# callisto_schematics_digital.net
KiCad netlist of a schematic drawn in Altium Designer
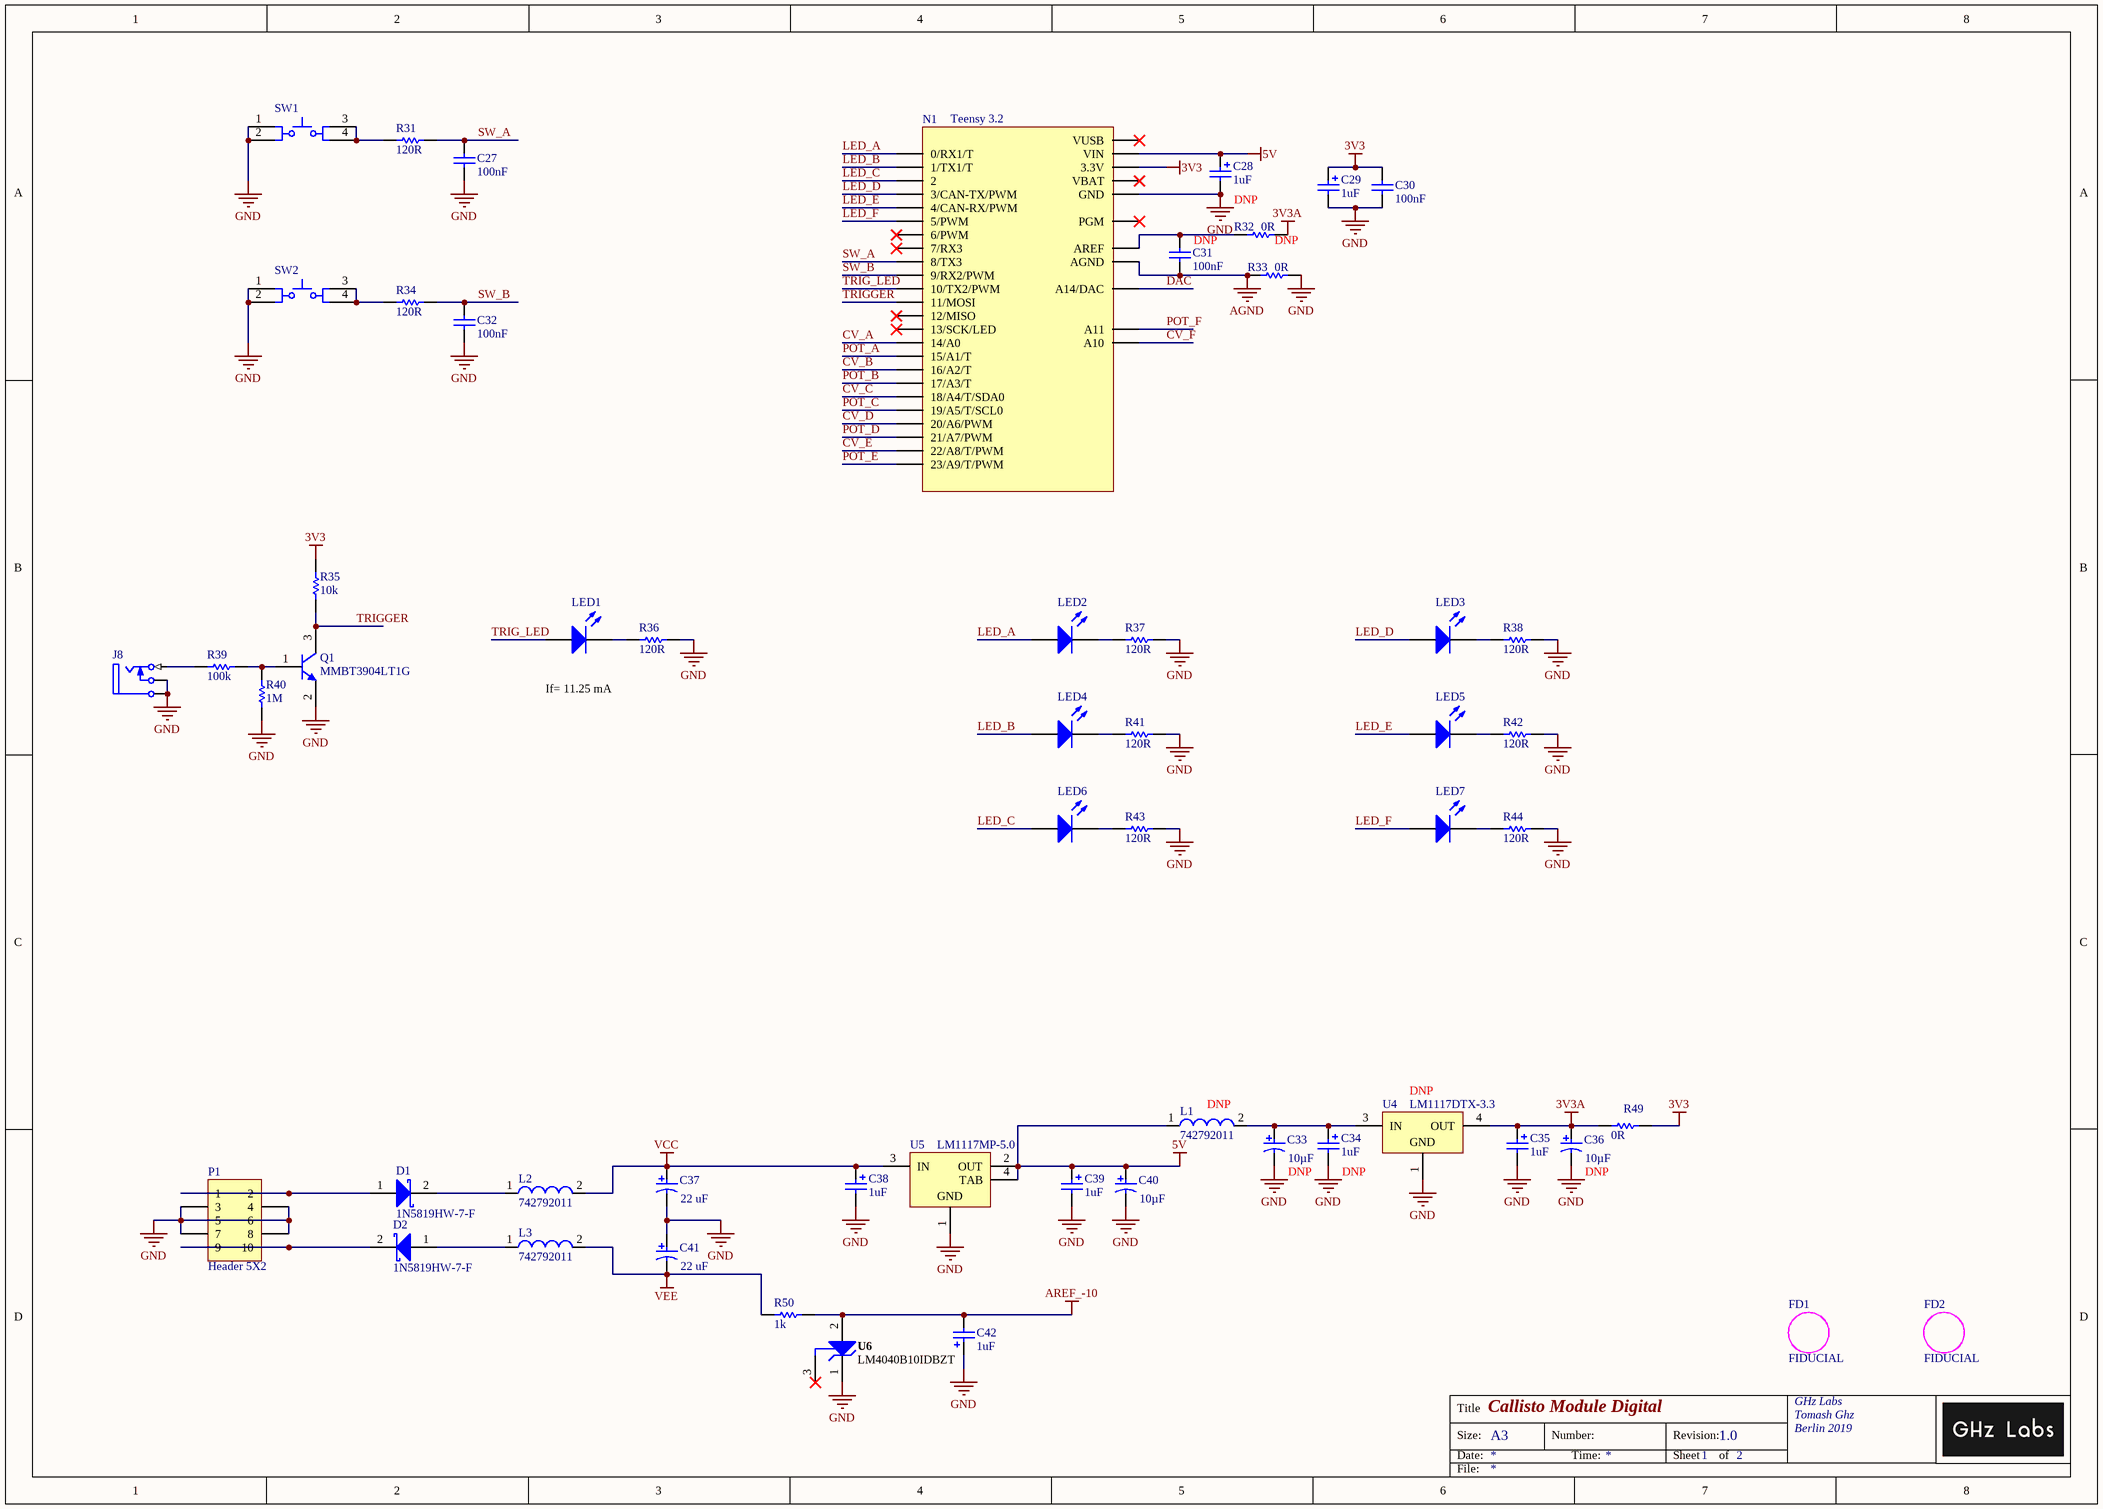
[diagram p0: callisto_schematics_digital.SchDoc]

(export (version "E")
  (design (tool "Eeschema 10.0.6"))
  (components
    (comp (ref "C27")
      (value "100nF")
      (footprint "GHzLabs_Parts:CAPA_0805")
      (description "Capacitor")
      (fields
        (field (name "PARTNUMBER") "C0805C104K4RAC")
        (field (name "MANUFACTURER") "KEMET")
        (field (name "PUBLISHER") "Altium Limited")
      )
      (libsource (lib "Miscellaneous Devices") (part "Cap"))
    )
    (comp (ref "C28")
      (value "1uF")
      (footprint "GHzLabs_Parts:CAPA_0805 Pol")
      (description "Polarized Capacitor")
      (fields
        (field (name "PARTNUMBER") "GRM21BR61C105KA01L")
        (field (name "MANUFACTURER") "Murata Electronics")
      )
      (libsource (lib "Miscellaneous Devices") (part "Cap Pol2"))
    )
    (comp (ref "C29")
      (value "1uF")
      (footprint "GHzLabs_Parts:CAPA_0805 Pol")
      (description "Polarized Capacitor")
      (fields
        (field (name "PARTNUMBER") "GRM21BR61C105KA01L")
        (field (name "MANUFACTURER") "Murata Electronics")
      )
      (libsource (lib "Miscellaneous Devices") (part "Cap Pol2"))
    )
    (comp (ref "C30")
      (value "100nF")
      (footprint "GHzLabs_Parts:CAPA_0805")
      (description "Capacitor")
      (fields
        (field (name "PARTNUMBER") "C0805C104K4RAC")
        (field (name "MANUFACTURER") "KEMET")
        (field (name "PUBLISHER") "Altium Limited")
      )
      (libsource (lib "Miscellaneous Devices") (part "Cap"))
    )
    (comp (ref "C31")
      (value "100nF")
      (footprint "GHzLabs_Parts:CAPA_0805")
      (description "Capacitor")
      (fields
        (field (name "PARTNUMBER") "C0805C104K4RAC")
        (field (name "MANUFACTURER") "KEMET")
        (field (name "PUBLISHER") "Altium Limited")
      )
      (libsource (lib "Miscellaneous Devices") (part "Cap"))
    )
    (comp (ref "C32")
      (value "100nF")
      (footprint "GHzLabs_Parts:CAPA_0805")
      (description "Capacitor")
      (fields
        (field (name "PARTNUMBER") "C0805C104K4RAC")
        (field (name "MANUFACTURER") "KEMET")
        (field (name "PUBLISHER") "Altium Limited")
      )
      (libsource (lib "Miscellaneous Devices") (part "Cap"))
    )
    (comp (ref "C33")
      (value "EEE-FK1V100UR")
      (footprint "PNSC-FK-V-B_V")
      (fields (field (name "MANUFACTURER") "Panasonic") (field (name "CAPACITANCE") "10µF"))
      (libsource (lib "Altium Content Vault") (part "CMP-2000-06211-1"))
    )
    (comp (ref "C34")
      (value "1uF")
      (footprint "GHzLabs_Parts:CAPA_0805 Pol")
      (description "Polarized Capacitor")
      (fields
        (field (name "PARTNUMBER") "GRM21BR61C105KA01L")
        (field (name "MANUFACTURER") "Murata Electronics")
      )
      (libsource (lib "Miscellaneous Devices") (part "Cap Pol2"))
    )
    (comp (ref "C35")
      (value "1uF")
      (footprint "GHzLabs_Parts:CAPA_0805 Pol")
      (description "Polarized Capacitor")
      (fields
        (field (name "PARTNUMBER") "GRM21BR61C105KA01L")
        (field (name "MANUFACTURER") "Murata Electronics")
      )
      (libsource (lib "Miscellaneous Devices") (part "Cap Pol2"))
    )
    (comp (ref "C36")
      (value "EEE-FK1V100UR")
      (footprint "PNSC-FK-V-B_V")
      (fields (field (name "MANUFACTURER") "Panasonic") (field (name "CAPACITANCE") "10µF"))
      (libsource (lib "Altium Content Vault") (part "CMP-2000-06211-1"))
    )
    (comp (ref "C37")
      (value "22uF Electrolytic Capacitor")
      (footprint "NIC-CAPA2-5X5.8_V")
      (fields
        (field (name "PARTNUMBER") "EEE-FK1V220R")
        (field (name "RATED CAPACITANCE") "22 uF")
        (field (name "MANUFACTURER") "Panasonic")
      )
      (libsource (lib "Altium Content Vault") (part "CMP-0687-00027-1"))
    )
    (comp (ref "C38")
      (value "1uF")
      (footprint "GHzLabs_Parts:CAPA_0805 Pol")
      (description "Polarized Capacitor")
      (fields
        (field (name "PARTNUMBER") "GRM21BR61C105KA01L")
        (field (name "MANUFACTURER") "Murata Electronics")
      )
      (libsource (lib "Miscellaneous Devices") (part "Cap Pol2"))
    )
    (comp (ref "C39")
      (value "1uF")
      (footprint "GHzLabs_Parts:CAPA_0805 Pol")
      (description "Polarized Capacitor")
      (fields
        (field (name "PARTNUMBER") "GRM21BR61C105KA01L")
        (field (name "MANUFACTURER") "Murata Electronics")
      )
      (libsource (lib "Miscellaneous Devices") (part "Cap Pol2"))
    )
    (comp (ref "C40")
      (value "10uF Electrolytic Capacitor")
      (footprint "PNSC-FK-V-B_V")
      (fields
        (field (name "MANUFACTURER") "Panasonic")
        (field (name "CAPACITANCE") "10µF")
        (field (name "PARTNUMBER") "EEE-FK1E100R")
      )
      (libsource (lib "Altium Content Vault") (part "CMP-2000-06211-1"))
    )
    (comp (ref "C41")
      (value "22uF Electrolytic Capacitor")
      (footprint "NIC-CAPA2-5X5.8_V")
      (fields
        (field (name "PARTNUMBER") "EEE-FK1V220R")
        (field (name "RATED CAPACITANCE") "22 uF")
        (field (name "MANUFACTURER") "Panasonic")
      )
      (libsource (lib "Altium Content Vault") (part "CMP-0687-00027-1"))
    )
    (comp (ref "C42")
      (value "1uF")
      (footprint "GHzLabs_Parts:CAPA_0805 Pol")
      (description "Polarized Capacitor")
      (fields
        (field (name "PARTNUMBER") "GRM21BR61C105KA01L")
        (field (name "MANUFACTURER") "Murata Electronics")
      )
      (libsource (lib "Miscellaneous Devices") (part "Cap Pol2"))
    )
    (comp (ref "D1")
      (value "1N5819HW-7-F")
      (footprint "DIOD-SOD-123-2_V")
      (fields (field (name "MANUFACTURER") "Diodes Inc"))
      (libsource (lib "Altium Content Vault") (part "DIOD-DSKY-A1K2-2"))
    )
    (comp (ref "D2")
      (value "1N5819HW-7-F")
      (footprint "DIOD-SOD-123-2_V")
      (fields (field (name "MANUFACTURER") "Diodes Inc"))
      (libsource (lib "Altium Content Vault") (part "DIOD-DSKY-A1K2-2"))
    )
    (comp (ref "FD1")
      (value "FIDUCIAL")
      (footprint "GHzLabs_Parts:FIDUCIAL")
      (description "Fiducial - Round 1.5 mm Top-Bottom")
      (fields (field (name "MANUFACTURER") "No Vendor"))
      (libsource (lib "GHzLabs_Parts") (part "FIDUCIAL_ROUND"))
    )
    (comp (ref "FD2")
      (value "FIDUCIAL")
      (footprint "GHzLabs_Parts:FIDUCIAL")
      (description "Fiducial - Round 1.5 mm Top-Bottom")
      (fields (field (name "MANUFACTURER") "No Vendor"))
      (libsource (lib "GHzLabs_Parts") (part "FIDUCIAL_ROUND"))
    )
    (comp (ref "J8")
      (value "Phonejack2 TN")
      (footprint "GHzLabs_Parts:Thonkiconn")
      (description "Jack Socket")
      (fields (field (name "PART") "ACJM-MV35-2S") (field (name "MANUFACTURER") "Thonk"))
      (libsource (lib "GHzLabs_Parts") (part "Phonejack2 TN"))
    )
    (comp (ref "L1")
      (value "742792011")
      (footprint "SMD-0805")
      (description "SMD EMI Suppression Ferrite Bead WE-CBF, Z = 10 Ohm")
      (libsource (lib "Altium Content Vault") (part "PAS-IND-INDUCTOR-2"))
    )
    (comp (ref "L2")
      (value "742792011")
      (footprint "SMD-0805")
      (description "SMD EMI Suppression Ferrite Bead WE-CBF, Z = 10 Ohm")
      (fields (field (name "MANUFACTURER") "Wurth Elektronik"))
      (libsource (lib "Altium Content Vault") (part "CMP-0220-00043-1"))
    )
    (comp (ref "L3")
      (value "742792011")
      (footprint "SMD-0805")
      (description "SMD EMI Suppression Ferrite Bead WE-CBF, Z = 10 Ohm")
      (fields (field (name "MANUFACTURER") "Wurth Elektronik"))
      (libsource (lib "Altium Content Vault") (part "CMP-0220-00043-1"))
    )
    (comp (ref "LED1")
      (value "WP424YDT")
      (footprint "Type 3mm")
      (description "THT LED round mono-color color lens, WL-TMRC, Bright Green")
      (fields (field (name "MANUFACTURER") "Kingbright"))
      (libsource (lib "Altium Content Vault") (part "CMP-1488-00001-1"))
    )
    (comp (ref "LED2")
      (value "WP424YDT")
      (footprint "Type 3mm")
      (description "THT LED round mono-color color lens, WL-TMRC, Bright Green")
      (fields (field (name "MANUFACTURER") "Kingbright"))
      (libsource (lib "Altium Content Vault") (part "CMP-1488-00001-1"))
    )
    (comp (ref "LED3")
      (value "WP424YDT")
      (footprint "Type 3mm")
      (description "THT LED round mono-color color lens, WL-TMRC, Bright Green")
      (fields (field (name "MANUFACTURER") "Kingbright"))
      (libsource (lib "Altium Content Vault") (part "CMP-1488-00001-1"))
    )
    (comp (ref "LED4")
      (value "WP424YDT")
      (footprint "Type 3mm")
      (description "THT LED round mono-color color lens, WL-TMRC, Bright Green")
      (fields (field (name "MANUFACTURER") "Kingbright"))
      (libsource (lib "Altium Content Vault") (part "CMP-1488-00001-1"))
    )
    (comp (ref "LED5")
      (value "WP424YDT")
      (footprint "Type 3mm")
      (description "THT LED round mono-color color lens, WL-TMRC, Bright Green")
      (fields (field (name "MANUFACTURER") "Kingbright"))
      (libsource (lib "Altium Content Vault") (part "CMP-1488-00001-1"))
    )
    (comp (ref "LED6")
      (value "WP424YDT")
      (footprint "Type 3mm")
      (description "THT LED round mono-color color lens, WL-TMRC, Bright Green")
      (fields (field (name "MANUFACTURER") "Kingbright"))
      (libsource (lib "Altium Content Vault") (part "CMP-1488-00001-1"))
    )
    (comp (ref "LED7")
      (value "WP424YDT")
      (footprint "Type 3mm")
      (description "THT LED round mono-color color lens, WL-TMRC, Bright Green")
      (fields (field (name "MANUFACTURER") "Kingbright"))
      (libsource (lib "Altium Content Vault") (part "CMP-1488-00001-1"))
    )
    (comp (ref "N1")
      (value "Teensy 3.2")
      (footprint "TEENSY_3.0-3.2&LC_ALL_PINS")
      (description "Teensy 3.2 MCU")
      (fields (field (name "PARTNUMBER") "DEV-13736") (field (name "MANUFACTURER") "SparkFun"))
      (libsource (lib "Teensy_3_and_LC_Series_Boards_v1") (part "TEENSY_3.1-3.2_ALL_PINS"))
    )
    (comp (ref "P1")
      (value "Header 5X2")
      (footprint "HDR2X5")
      (description "Header, 5-Pin, Dual row")
      (fields
        (field (name "PARTNUMBER") "67996-410HLF")
        (field (name "MANUFACTURER") "FCI Amphenol")
        (field (name "PUBLISHER") "Altium Limited")
      )
      (libsource (lib "Miscellaneous Connectors") (part "Header 5X2"))
    )
    (comp (ref "Q1")
      (value "MMBT3904LT1G")
      (footprint "ONSC-SOT-23-3-318-08_V")
      (description "General Purpose Transistor, NPN Silicon, 3-Pin SOT-23, Pb-Free, Tape and Reel")
      (fields (field (name "MANUFACTURER") "On Semiconductor"))
      (libsource (lib "Altium Content Vault") (part "ONSC-NPN-B1E2C3-3"))
    )
    (comp (ref "R31")
      (value "120R")
      (footprint "GHzLabs_Parts:RES_0805")
      (description "120R 0805")
      (fields (field (name "PARTNUMBER") "CRCW0805120RJNEA") (field (name "MANUFACTURER") "Vishay"))
      (libsource (lib "GHzLabs_Parts") (part "Resistor"))
    )
    (comp (ref "R32")
      (value "0R")
      (footprint "GHzLabs_Parts:RES_0805")
      (description "0R 0805")
      (fields (field (name "PARTNUMBER") "CRCW08050000Z0EA") (field (name "MANUFACTURER") "Vishay"))
      (libsource (lib "myParts") (part "Resistor"))
    )
    (comp (ref "R33")
      (value "0R")
      (footprint "GHzLabs_Parts:RES_0805")
      (description "0R 0805")
      (fields (field (name "PARTNUMBER") "CRCW08050000Z0EA") (field (name "MANUFACTURER") "Vishay"))
      (libsource (lib "myParts") (part "Resistor"))
    )
    (comp (ref "R34")
      (value "120R")
      (footprint "GHzLabs_Parts:RES_0805")
      (description "120R 0805")
      (fields (field (name "PARTNUMBER") "CRCW0805120RJNEA") (field (name "MANUFACTURER") "Vishay"))
      (libsource (lib "GHzLabs_Parts") (part "Resistor"))
    )
    (comp (ref "R35")
      (value "10k")
      (footprint "GHzLabs_Parts:RES_0805")
      (description "10k 0805")
      (fields (field (name "PARTNUMBER") "RR1220P-103-D") (field (name "MANUFACTURER") "Susumu"))
      (libsource (lib "GHzLabs_Parts") (part "Resistor"))
    )
    (comp (ref "R36")
      (value "120R")
      (footprint "GHzLabs_Parts:RES_0805")
      (description "120R 0805")
      (fields (field (name "PARTNUMBER") "CRCW0805120RJNEA") (field (name "MANUFACTURER") "Vishay"))
      (libsource (lib "GHzLabs_Parts") (part "Resistor"))
    )
    (comp (ref "R37")
      (value "120R")
      (footprint "GHzLabs_Parts:RES_0805")
      (description "120R 0805")
      (fields (field (name "PARTNUMBER") "CRCW0805120RJNEA") (field (name "MANUFACTURER") "Vishay"))
      (libsource (lib "GHzLabs_Parts") (part "Resistor"))
    )
    (comp (ref "R38")
      (value "120R")
      (footprint "GHzLabs_Parts:RES_0805")
      (description "120R 0805")
      (fields (field (name "PARTNUMBER") "CRCW0805120RJNEA") (field (name "MANUFACTURER") "Vishay"))
      (libsource (lib "GHzLabs_Parts") (part "Resistor"))
    )
    (comp (ref "R39")
      (value "100k")
      (footprint "GHzLabs_Parts:RES_0805")
      (description "100k 0805")
      (fields (field (name "PARTNUMBER") "RR1220P-104-D") (field (name "MANUFACTURER") "Susumu"))
      (libsource (lib "GHzLabs_Parts") (part "Resistor"))
    )
    (comp (ref "R40")
      (value "1M")
      (footprint "GHzLabs_Parts:RES_0805")
      (description "1M 0805")
      (fields (field (name "PARTNUMBER") "RR1220P-105-D") (field (name "MANUFACTURER") "Susumu"))
      (libsource (lib "GHzLabs_Parts") (part "Resistor"))
    )
    (comp (ref "R41")
      (value "120R")
      (footprint "GHzLabs_Parts:RES_0805")
      (description "120R 0805")
      (fields (field (name "PARTNUMBER") "CRCW0805120RJNEA") (field (name "MANUFACTURER") "Vishay"))
      (libsource (lib "GHzLabs_Parts") (part "Resistor"))
    )
    (comp (ref "R42")
      (value "120R")
      (footprint "GHzLabs_Parts:RES_0805")
      (description "120R 0805")
      (fields (field (name "PARTNUMBER") "CRCW0805120RJNEA") (field (name "MANUFACTURER") "Vishay"))
      (libsource (lib "GHzLabs_Parts") (part "Resistor"))
    )
    (comp (ref "R43")
      (value "120R")
      (footprint "GHzLabs_Parts:RES_0805")
      (description "120R 0805")
      (fields (field (name "PARTNUMBER") "CRCW0805120RJNEA") (field (name "MANUFACTURER") "Vishay"))
      (libsource (lib "GHzLabs_Parts") (part "Resistor"))
    )
    (comp (ref "R44")
      (value "120R")
      (footprint "GHzLabs_Parts:RES_0805")
      (description "120R 0805")
      (fields (field (name "PARTNUMBER") "CRCW0805120RJNEA") (field (name "MANUFACTURER") "Vishay"))
      (libsource (lib "GHzLabs_Parts") (part "Resistor"))
    )
    (comp (ref "R49")
      (value "0R")
      (footprint "GHzLabs_Parts:RES_0805")
      (description "0R 0805")
      (fields (field (name "PARTNUMBER") "CRCW08050000Z0EA") (field (name "MANUFACTURER") "Vishay"))
      (libsource (lib "myParts") (part "Resistor"))
    )
    (comp (ref "R50")
      (value "1k")
      (footprint "GHzLabs_Parts:RES_0805")
      (description "1k 0805")
      (fields (field (name "PARTNUMBER") "RR1220P-102-D") (field (name "MANUFACTURER") "Susumu"))
      (libsource (lib "myParts") (part "Resistor"))
    )
    (comp (ref "SW1")
      (value "Tact Switch")
      (footprint "ESWI-TL1105SPF_V")
      (description "Tact Switch, SPST-NO, 50 mA, 12 VDC, -20 to 70 degC, 4-Pin THD, RoHS, Bulk")
      (fields (field (name "MANUFACTURER") "E-Switch") (field (name "PARTNUMBER") "TL1105SPF100Q"))
      (libsource (lib "Altium Content Vault") (part "CMP-2000-07248-1"))
    )
    (comp (ref "SW2")
      (value "Tact Switch")
      (footprint "ESWI-TL1105SPF_V")
      (description "Tact Switch, SPST-NO, 50 mA, 12 VDC, -20 to 70 degC, 4-Pin THD, RoHS, Bulk")
      (fields (field (name "MANUFACTURER") "E-Switch") (field (name "PARTNUMBER") "TL1105SPF100Q"))
      (libsource (lib "Altium Content Vault") (part "CMP-2000-07248-1"))
    )
    (comp (ref "U4")
      (value "LM1117DTX-3.3")
      (footprint "TD03B_M")
      (description "800mA Low-Dropout Linear Regulator, 3-pin TO-252")
      (fields (field (name "MANUFACTURER") "National Semiconductor"))
      (libsource (lib "Altium Content Vault") (part "CMP-0062-00706-2"))
    )
    (comp (ref "U5")
      (value "LM1117MP-5.0")
      (footprint "MP04A_M")
      (description "800mA Low-Dropout Linear Regulator, 4-pin SOT-223")
      (fields (field (name "MANUFACTURER") "National Semiconductor"))
      (libsource (lib "Altium Content Vault") (part "CMP-0062-01640-3"))
    )
    (comp (ref "U6")
      (value "LM4040B10IDBZT")
      (footprint "DBZ0003A_M")
      (fields (field (name "MANUFACTURER") "Texas Instruments"))
      (libsource (lib "Altium Content Vault") (part "CMP-0366-01043-2"))
    )
  )
  (nets
    (net (code "1") (name "/CV_A") (class "Default")
      (node (ref "N1") (pin "14/A0") (pinfunction "14/A0_14/A0") (pintype "passive"))
    )
    (net (code "2") (name "/CV_B") (class "Default")
      (node (ref "N1") (pin "16/A2") (pinfunction "16/A2/T_16/A2") (pintype "passive"))
    )
    (net (code "3") (name "/CV_C") (class "Default")
      (node (ref "N1") (pin "18/A4") (pinfunction "18/A4/T/SDA0_18/A4") (pintype "passive"))
    )
    (net (code "4") (name "/CV_D") (class "Default")
      (node (ref "N1") (pin "20/A6") (pinfunction "20/A6/PWM_20/A6") (pintype "passive"))
    )
    (net (code "5") (name "/CV_E") (class "Default")
      (node (ref "N1") (pin "22/A8") (pinfunction "22/A8/T/PWM_22/A8") (pintype "passive"))
    )
    (net (code "6") (name "/CV_F") (class "Default")
      (node (ref "N1") (pin "A10") (pinfunction "A10_A10") (pintype "passive"))
    )
    (net (code "7") (name "/DAC") (class "Default")
      (node (ref "N1") (pin "RESET/DAC") (pinfunction "A14/DAC_RESET/DAC") (pintype "passive"))
    )
    (net (code "8") (name "/LED_A") (class "Default")
      (node (ref "LED2") (pin "2") (pinfunction "A_2") (pintype "passive"))
      (node (ref "N1") (pin "0") (pinfunction "0/RX1/T_0") (pintype "passive"))
    )
    (net (code "9") (name "/LED_B") (class "Default")
      (node (ref "LED4") (pin "2") (pinfunction "A_2") (pintype "passive"))
      (node (ref "N1") (pin "1") (pinfunction "1/TX1/T_1") (pintype "passive"))
    )
    (net (code "10") (name "/LED_C") (class "Default")
      (node (ref "LED6") (pin "2") (pinfunction "A_2") (pintype "passive"))
      (node (ref "N1") (pin "2") (pinfunction "2_2") (pintype "passive"))
    )
    (net (code "11") (name "/LED_D") (class "Default")
      (node (ref "LED3") (pin "2") (pinfunction "A_2") (pintype "passive"))
      (node (ref "N1") (pin "3") (pinfunction "3/CAN-TX/PWM_3") (pintype "passive"))
    )
    (net (code "12") (name "/LED_E") (class "Default")
      (node (ref "LED5") (pin "2") (pinfunction "A_2") (pintype "passive"))
      (node (ref "N1") (pin "4") (pinfunction "4/CAN-RX/PWM_4") (pintype "passive"))
    )
    (net (code "13") (name "/LED_F") (class "Default")
      (node (ref "LED7") (pin "2") (pinfunction "A_2") (pintype "passive"))
      (node (ref "N1") (pin "5") (pinfunction "5/PWM_5") (pintype "passive"))
    )
    (net (code "14") (name "/POT_A") (class "Default")
      (node (ref "N1") (pin "15/A1") (pinfunction "15/A1/T_15/A1") (pintype "passive"))
    )
    (net (code "15") (name "/POT_B") (class "Default")
      (node (ref "N1") (pin "17/A3") (pinfunction "17/A3/T_17/A3") (pintype "passive"))
    )
    (net (code "16") (name "/POT_C") (class "Default")
      (node (ref "N1") (pin "19/A5") (pinfunction "19/A5/T/SCL0_19/A5") (pintype "passive"))
    )
    (net (code "17") (name "/POT_D") (class "Default")
      (node (ref "N1") (pin "21/A7") (pinfunction "21/A7/PWM_21/A7") (pintype "passive"))
    )
    (net (code "18") (name "/POT_E") (class "Default")
      (node (ref "N1") (pin "23/A9") (pinfunction "23/A9/T/PWM_23/A9") (pintype "passive"))
    )
    (net (code "19") (name "/POT_F") (class "Default")
      (node (ref "N1") (pin "A11") (pinfunction "A11_A11") (pintype "passive"))
    )
    (net (code "20") (name "/SW_A") (class "Default")
      (node (ref "C27") (pin "1") (pinfunction "1_1") (pintype "passive"))
      (node (ref "N1") (pin "8") (pinfunction "8/TX3_8") (pintype "passive"))
      (node (ref "R31") (pin "1") (pinfunction "1_1") (pintype "passive"))
    )
    (net (code "21") (name "/SW_B") (class "Default")
      (node (ref "C32") (pin "1") (pinfunction "1_1") (pintype "passive"))
      (node (ref "N1") (pin "9") (pinfunction "9/RX2/PWM_9") (pintype "passive"))
      (node (ref "R34") (pin "1") (pinfunction "1_1") (pintype "passive"))
    )
    (net (code "22") (name "/TRIGGER") (class "Default")
      (node (ref "N1") (pin "11") (pinfunction "11/MOSI_11") (pintype "passive"))
      (node (ref "Q1") (pin "3") (pinfunction "C_3") (pintype "passive"))
      (node (ref "R35") (pin "2") (pinfunction "2_2") (pintype "passive"))
    )
    (net (code "23") (name "/TRIG_LED") (class "Default")
      (node (ref "LED1") (pin "2") (pinfunction "A_2") (pintype "passive"))
      (node (ref "N1") (pin "10") (pinfunction "10/TX2/PWM_10") (pintype "passive"))
    )
    (net (code "24") (name "3V3") (class "Default")
      (node (ref "C29") (pin "1") (pinfunction "1_1") (pintype "passive"))
      (node (ref "C30") (pin "1") (pinfunction "1_1") (pintype "passive"))
      (node (ref "N1") (pin "3.3V_3.3V1") (pinfunction "3.3V_3.3V_3.3V1") (pintype "power_in"))
      (node (ref "R35") (pin "1") (pinfunction "1_1") (pintype "passive"))
      (node (ref "R49") (pin "2") (pinfunction "2_2") (pintype "passive"))
    )
    (net (code "25") (name "3V3A") (class "Default")
      (node (ref "C35") (pin "1") (pinfunction "1_1") (pintype "passive"))
      (node (ref "C36") (pin "1") (pinfunction "1_1") (pintype "passive"))
      (node (ref "R32") (pin "2") (pinfunction "2_2") (pintype "passive"))
      (node (ref "R49") (pin "1") (pinfunction "1_1") (pintype "passive"))
      (node (ref "U4") (pin "4") (pinfunction "OUT_4") (pintype "power_in"))
    )
    (net (code "26") (name "5V") (class "Default")
      (node (ref "C28") (pin "1") (pinfunction "1_1") (pintype "passive"))
      (node (ref "C39") (pin "1") (pinfunction "1_1") (pintype "passive"))
      (node (ref "C40") (pin "1") (pinfunction "1_1") (pintype "passive"))
      (node (ref "L1") (pin "1") (pinfunction "1_1") (pintype "passive"))
      (node (ref "N1") (pin "VIN") (pinfunction "VIN_VIN") (pintype "power_in"))
      (node (ref "U5") (pin "2") (pinfunction "OUT_2") (pintype "power_in"))
      (node (ref "U5") (pin "4") (pinfunction "TAB_4") (pintype "power_in"))
    )
    (net (code "27") (name "AGND") (class "Default")
      (node (ref "C31") (pin "2") (pinfunction "2_2") (pintype "passive"))
      (node (ref "N1") (pin "AGND") (pinfunction "AGND_AGND") (pintype "power_in"))
      (node (ref "R33") (pin "1") (pinfunction "1_1") (pintype "passive"))
    )
    (net (code "28") (name "AREF_-10") (class "Default")
      (node (ref "C42") (pin "2") (pinfunction "2_2") (pintype "passive"))
      (node (ref "R50") (pin "1") (pinfunction "1_1") (pintype "passive"))
      (node (ref "U6") (pin "2") (pinfunction "ANODE_2") (pintype "passive"))
    )
    (net (code "29") (name "GND") (class "Default")
      (node (ref "C27") (pin "2") (pinfunction "2_2") (pintype "passive"))
      (node (ref "C28") (pin "2") (pinfunction "2_2") (pintype "passive"))
      (node (ref "C29") (pin "2") (pinfunction "2_2") (pintype "passive"))
      (node (ref "C30") (pin "2") (pinfunction "2_2") (pintype "passive"))
      (node (ref "C32") (pin "2") (pinfunction "2_2") (pintype "passive"))
      (node (ref "C33") (pin "2") (pinfunction "2_2") (pintype "passive"))
      (node (ref "C34") (pin "2") (pinfunction "2_2") (pintype "passive"))
      (node (ref "C35") (pin "2") (pinfunction "2_2") (pintype "passive"))
      (node (ref "C36") (pin "2") (pinfunction "2_2") (pintype "passive"))
      (node (ref "C37") (pin "2") (pinfunction "2_2") (pintype "passive"))
      (node (ref "C38") (pin "2") (pinfunction "2_2") (pintype "passive"))
      (node (ref "C39") (pin "2") (pinfunction "2_2") (pintype "passive"))
      (node (ref "C40") (pin "2") (pinfunction "2_2") (pintype "passive"))
      (node (ref "C41") (pin "1") (pinfunction "1_1") (pintype "passive"))
      (node (ref "C42") (pin "1") (pinfunction "1_1") (pintype "passive"))
      (node (ref "J8") (pin "2") (pinfunction "TN_2") (pintype "passive"))
      (node (ref "J8") (pin "5") (pinfunction "S_5") (pintype "power_in"))
      (node (ref "N1") (pin "GND_GND1") (pinfunction "GND_GND_GND1") (pintype "power_in"))
      (node (ref "P1") (pin "3") (pinfunction "3_3") (pintype "passive"))
      (node (ref "P1") (pin "4") (pinfunction "4_4") (pintype "passive"))
      (node (ref "P1") (pin "5") (pinfunction "5_5") (pintype "passive"))
      (node (ref "P1") (pin "6") (pinfunction "6_6") (pintype "passive"))
      (node (ref "P1") (pin "7") (pinfunction "7_7") (pintype "passive"))
      (node (ref "P1") (pin "8") (pinfunction "8_8") (pintype "passive"))
      (node (ref "Q1") (pin "2") (pinfunction "E_2") (pintype "passive"))
      (node (ref "R33") (pin "2") (pinfunction "2_2") (pintype "passive"))
      (node (ref "R36") (pin "1") (pinfunction "1_1") (pintype "passive"))
      (node (ref "R37") (pin "1") (pinfunction "1_1") (pintype "passive"))
      (node (ref "R38") (pin "1") (pinfunction "1_1") (pintype "passive"))
      (node (ref "R40") (pin "2") (pinfunction "2_2") (pintype "passive"))
      (node (ref "R41") (pin "1") (pinfunction "1_1") (pintype "passive"))
      (node (ref "R42") (pin "1") (pinfunction "1_1") (pintype "passive"))
      (node (ref "R43") (pin "1") (pinfunction "1_1") (pintype "passive"))
      (node (ref "R44") (pin "1") (pinfunction "1_1") (pintype "passive"))
      (node (ref "SW1") (pin "1") (pinfunction "1_1") (pintype "passive"))
      (node (ref "SW1") (pin "2") (pinfunction "2_2") (pintype "passive"))
      (node (ref "SW2") (pin "1") (pinfunction "1_1") (pintype "passive"))
      (node (ref "SW2") (pin "2") (pinfunction "2_2") (pintype "passive"))
      (node (ref "U4") (pin "1") (pinfunction "GND_1") (pintype "power_in"))
      (node (ref "U5") (pin "1") (pinfunction "GND_1") (pintype "power_in"))
      (node (ref "U6") (pin "1") (pinfunction "CATHODE_1") (pintype "passive"))
    )
    (net (code "30") (name "Net-(C31-Pad1)") (class "Default")
      (node (ref "C31") (pin "1") (pinfunction "1_1") (pintype "passive"))
      (node (ref "N1") (pin "AREF") (pinfunction "AREF_AREF") (pintype "power_in"))
      (node (ref "R32") (pin "1") (pinfunction "1_1") (pintype "passive"))
    )
    (net (code "31") (name "Net-(D1-A)") (class "Default")
      (node (ref "D1") (pin "1") (pinfunction "A_1") (pintype "passive"))
      (node (ref "P1") (pin "1") (pinfunction "1_1") (pintype "passive"))
      (node (ref "P1") (pin "2") (pinfunction "2_2") (pintype "passive"))
    )
    (net (code "32") (name "Net-(D1-K)") (class "Default")
      (node (ref "D1") (pin "2") (pinfunction "K_2") (pintype "passive"))
      (node (ref "L2") (pin "1") (pinfunction "1_1") (pintype "passive"))
    )
    (net (code "33") (name "Net-(D2-A)") (class "Default")
      (node (ref "D2") (pin "1") (pinfunction "A_1") (pintype "passive"))
      (node (ref "L3") (pin "1") (pinfunction "1_1") (pintype "passive"))
    )
    (net (code "34") (name "Net-(D2-K)") (class "Default")
      (node (ref "D2") (pin "2") (pinfunction "K_2") (pintype "passive"))
      (node (ref "P1") (pin "10") (pinfunction "10_10") (pintype "passive"))
      (node (ref "P1") (pin "9") (pinfunction "9_9") (pintype "passive"))
    )
    (net (code "35") (name "Net-(J8-T)") (class "Default")
      (node (ref "J8") (pin "1") (pinfunction "T_1") (pintype "input"))
      (node (ref "R39") (pin "2") (pinfunction "2_2") (pintype "passive"))
    )
    (net (code "36") (name "Net-(LED1-K)") (class "Default")
      (node (ref "LED1") (pin "1") (pinfunction "K_1") (pintype "passive"))
      (node (ref "R36") (pin "2") (pinfunction "2_2") (pintype "passive"))
    )
    (net (code "37") (name "Net-(LED2-K)") (class "Default")
      (node (ref "LED2") (pin "1") (pinfunction "K_1") (pintype "passive"))
      (node (ref "R37") (pin "2") (pinfunction "2_2") (pintype "passive"))
    )
    (net (code "38") (name "Net-(LED3-K)") (class "Default")
      (node (ref "LED3") (pin "1") (pinfunction "K_1") (pintype "passive"))
      (node (ref "R38") (pin "2") (pinfunction "2_2") (pintype "passive"))
    )
    (net (code "39") (name "Net-(LED4-K)") (class "Default")
      (node (ref "LED4") (pin "1") (pinfunction "K_1") (pintype "passive"))
      (node (ref "R41") (pin "2") (pinfunction "2_2") (pintype "passive"))
    )
    (net (code "40") (name "Net-(LED5-K)") (class "Default")
      (node (ref "LED5") (pin "1") (pinfunction "K_1") (pintype "passive"))
      (node (ref "R42") (pin "2") (pinfunction "2_2") (pintype "passive"))
    )
    (net (code "41") (name "Net-(LED6-K)") (class "Default")
      (node (ref "LED6") (pin "1") (pinfunction "K_1") (pintype "passive"))
      (node (ref "R43") (pin "2") (pinfunction "2_2") (pintype "passive"))
    )
    (net (code "42") (name "Net-(LED7-K)") (class "Default")
      (node (ref "LED7") (pin "1") (pinfunction "K_1") (pintype "passive"))
      (node (ref "R44") (pin "2") (pinfunction "2_2") (pintype "passive"))
    )
    (net (code "43") (name "Net-(Q1-B)") (class "Default")
      (node (ref "Q1") (pin "1") (pinfunction "B_1") (pintype "passive"))
      (node (ref "R39") (pin "1") (pinfunction "1_1") (pintype "passive"))
      (node (ref "R40") (pin "1") (pinfunction "1_1") (pintype "passive"))
    )
    (net (code "44") (name "Net-(R31-Pad2)") (class "Default")
      (node (ref "R31") (pin "2") (pinfunction "2_2") (pintype "passive"))
      (node (ref "SW1") (pin "3") (pinfunction "3_3") (pintype "passive"))
      (node (ref "SW1") (pin "4") (pinfunction "4_4") (pintype "passive"))
    )
    (net (code "45") (name "Net-(R34-Pad2)") (class "Default")
      (node (ref "R34") (pin "2") (pinfunction "2_2") (pintype "passive"))
      (node (ref "SW2") (pin "3") (pinfunction "3_3") (pintype "passive"))
      (node (ref "SW2") (pin "4") (pinfunction "4_4") (pintype "passive"))
    )
    (net (code "46") (name "Net-(U4-IN)") (class "Default")
      (node (ref "C33") (pin "1") (pinfunction "1_1") (pintype "passive"))
      (node (ref "C34") (pin "1") (pinfunction "1_1") (pintype "passive"))
      (node (ref "L1") (pin "2") (pinfunction "2_2") (pintype "passive"))
      (node (ref "U4") (pin "3") (pinfunction "IN_3") (pintype "power_in"))
    )
    (net (code "47") (name "VCC") (class "Default")
      (node (ref "C37") (pin "1") (pinfunction "1_1") (pintype "passive"))
      (node (ref "C38") (pin "1") (pinfunction "1_1") (pintype "passive"))
      (node (ref "L2") (pin "2") (pinfunction "2_2") (pintype "passive"))
      (node (ref "U5") (pin "3") (pinfunction "IN_3") (pintype "power_in"))
    )
    (net (code "48") (name "VEE") (class "Default")
      (node (ref "C41") (pin "2") (pinfunction "2_2") (pintype "passive"))
      (node (ref "L3") (pin "2") (pinfunction "2_2") (pintype "passive"))
      (node (ref "R50") (pin "2") (pinfunction "2_2") (pintype "passive"))
    )
    (net (code "49") (name "unconnected-(N1-6{slash}PWM-Pad6)") (class "Default")
      (node (ref "N1") (pin "6") (pinfunction "6/PWM_6") (pintype "passive+no_connect"))
    )
    (net (code "50") (name "unconnected-(N1-7{slash}RX3-Pad7)") (class "Default")
      (node (ref "N1") (pin "7") (pinfunction "7/RX3_7") (pintype "passive+no_connect"))
    )
    (net (code "51") (name "unconnected-(N1-12{slash}MISO-Pad12)") (class "Default")
      (node (ref "N1") (pin "12") (pinfunction "12/MISO_12") (pintype "passive+no_connect"))
    )
    (net (code "52") (name "unconnected-(N1-13{slash}SCK{slash}LED-Pad13)") (class "Default")
      (node (ref "N1") (pin "13") (pinfunction "13/SCK/LED_13") (pintype "passive+no_connect"))
    )
    (net (code "53") (name "unconnected-(N1-PadPGM)") (class "Default")
      (node (ref "N1") (pin "PGM") (pinfunction "PGM_PGM") (pintype "passive+no_connect"))
    )
    (net (code "54") (name "unconnected-(N1-PadVBAT)") (class "Default")
      (node (ref "N1") (pin "VBAT") (pinfunction "VBAT_VBAT") (pintype "power_in+no_connect"))
    )
    (net (code "55") (name "unconnected-(N1-PadVUSB)") (class "Default")
      (node (ref "N1") (pin "VUSB") (pinfunction "VUSB_VUSB") (pintype "power_in+no_connect"))
    )
    (net (code "56") (name "unconnected-(U6-NC-Pad3)") (class "Default")
      (node (ref "U6") (pin "3") (pinfunction "NC_3") (pintype "passive+no_connect"))
    )
  )
)
